# remotecontrol.net
KiCad netlist of a schematic drawn in EAGLE
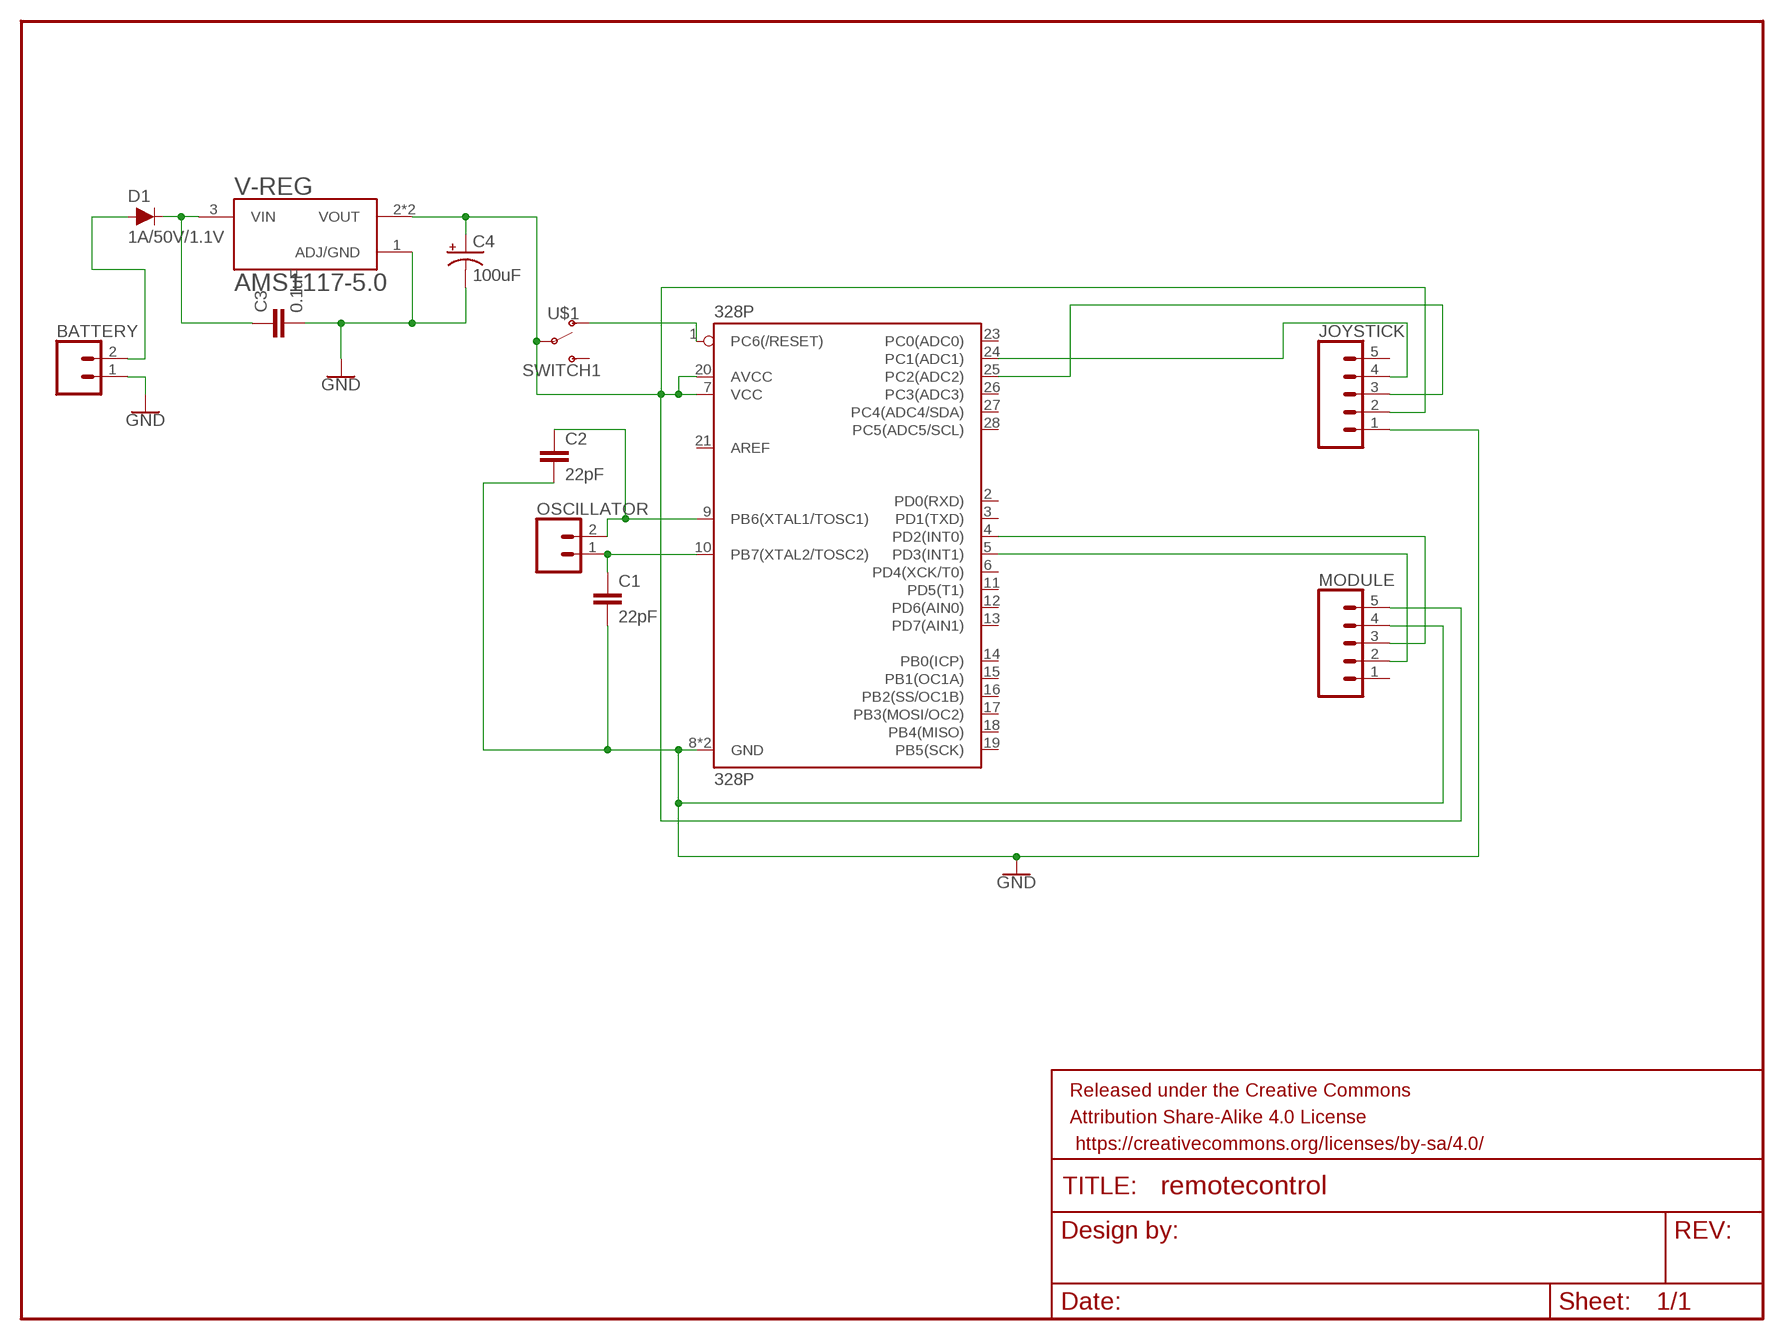
[diagram p0: schematic, sheet 1]

(export (version "E")
  (design (tool "Eeschema 10.0.6"))
  (components
    (comp (ref "328P")
      (value "328P")
      (footprint "eagle-import:DIP28")
      (libsource (lib "eagle-import") (part "ATMEGA328P_PDIP"))
    )
    (comp (ref "BATTERY")
      (value "CONN_02")
      (footprint "eagle-import:1X02")
      (libsource (lib "eagle-import") (part "CONN_02"))
    )
    (comp (ref "C1")
      (value "22pF")
      (footprint "eagle-import:0603")
      (libsource (lib "eagle-import") (part "22PF-0603-50V-5%"))
    )
    (comp (ref "C2")
      (value "22pF")
      (footprint "eagle-import:0603")
      (libsource (lib "eagle-import") (part "22PF-0603-50V-5%"))
    )
    (comp (ref "C3")
      (value "0.1uF")
      (footprint "eagle-import:0603")
      (libsource (lib "eagle-import") (part "0.1UF-0603-25V-(+80/-20%)"))
    )
    (comp (ref "C4")
      (value "100uF")
      (footprint "eagle-import:NIC_10X10.5_CAP")
      (libsource (lib "eagle-import") (part "100UF-POLAR-10X10.5-63V-20%"))
    )
    (comp (ref "D1")
      (value "1A/50V/1.1V")
      (footprint "eagle-import:DIODE-1N4001")
      (libsource (lib "eagle-import") (part "DIODE-PTH"))
    )
    (comp (ref "FRAME1")
      (value "FRAME-LETTER")
      (footprint "eagle-import:CREATIVE_COMMONS")
      (libsource (lib "eagle-import") (part "FRAME-LETTER"))
    )
    (comp (ref "JOYSTICK")
      (value "CONN_05")
      (footprint "eagle-import:1X05")
      (libsource (lib "eagle-import") (part "CONN_05"))
    )
    (comp (ref "MODULE")
      (value "CONN_05")
      (footprint "eagle-import:1X05")
      (libsource (lib "eagle-import") (part "CONN_05"))
    )
    (comp (ref "OSCILLATOR")
      (value "CONN_02")
      (footprint "eagle-import:1X02")
      (libsource (lib "eagle-import") (part "CONN_02"))
    )
    (comp (ref "U$1")
      (value "SWITCH1")
      (footprint "eagle-import:SWITCH1")
      (libsource (lib "eagle-import") (part "SWITCH1"))
    )
    (comp (ref "V-REG")
      (value "AMS1117-5.0")
      (footprint "eagle-import:SOT229P700X180-4N")
      (fields (field (name "MF") "Advanced Monolithic Systems"))
      (libsource (lib "eagle-import") (part "AMS1117-5.0"))
    )
  )
  (nets
    (net (code "1") (name "GND") (class "Default")
      (node (ref "328P") (pin "22") (pinfunction "GND_22") (pintype "bidirectional"))
      (node (ref "328P") (pin "8") (pinfunction "GND_8") (pintype "bidirectional"))
      (node (ref "BATTERY") (pin "1") (pinfunction "1_1") (pintype "passive"))
      (node (ref "C1") (pin "2") (pinfunction "2_2") (pintype "passive"))
      (node (ref "C2") (pin "2") (pinfunction "2_2") (pintype "passive"))
      (node (ref "C3") (pin "2") (pinfunction "2_2") (pintype "passive"))
      (node (ref "C4") (pin "-") (pinfunction "-_-") (pintype "passive"))
      (node (ref "JOYSTICK") (pin "1") (pinfunction "1_1") (pintype "passive"))
      (node (ref "MODULE") (pin "4") (pinfunction "4_4") (pintype "passive"))
      (node (ref "V-REG") (pin "1") (pinfunction "ADJ/GND_1") (pintype "power_in"))
    )
    (net (code "2") (name "Net-(328P-AVCC)") (class "Default")
      (node (ref "328P") (pin "20") (pinfunction "AVCC_20") (pintype "bidirectional"))
      (node (ref "328P") (pin "7") (pinfunction "VCC_7") (pintype "bidirectional"))
      (node (ref "C4") (pin "+") (pinfunction "+_+") (pintype "passive"))
      (node (ref "JOYSTICK") (pin "2") (pinfunction "2_2") (pintype "passive"))
      (node (ref "MODULE") (pin "5") (pinfunction "5_5") (pintype "passive"))
      (node (ref "U$1") (pin "P$2") (pinfunction "P_P$2") (pintype "passive"))
      (node (ref "V-REG") (pin "2") (pinfunction "VOUT_2") (pintype "output"))
      (node (ref "V-REG") (pin "4") (pinfunction "VOUT_4") (pintype "output"))
    )
    (net (code "3") (name "Net-(328P-PB6(XTAL1{slash}TOSC1))") (class "Default")
      (node (ref "328P") (pin "9") (pinfunction "PB6(XTAL1/TOSC1)_9") (pintype "bidirectional"))
      (node (ref "C2") (pin "1") (pinfunction "1_1") (pintype "passive"))
      (node (ref "OSCILLATOR") (pin "2") (pinfunction "2_2") (pintype "passive"))
    )
    (net (code "4") (name "Net-(328P-PB7(XTAL2{slash}TOSC2))") (class "Default")
      (node (ref "328P") (pin "10") (pinfunction "PB7(XTAL2/TOSC2)_10") (pintype "bidirectional"))
      (node (ref "C1") (pin "1") (pinfunction "1_1") (pintype "passive"))
      (node (ref "OSCILLATOR") (pin "1") (pinfunction "1_1") (pintype "passive"))
    )
    (net (code "5") (name "Net-(328P-PC1(ADC1))") (class "Default")
      (node (ref "328P") (pin "24") (pinfunction "PC1(ADC1)_24") (pintype "bidirectional"))
      (node (ref "JOYSTICK") (pin "4") (pinfunction "4_4") (pintype "passive"))
    )
    (net (code "6") (name "Net-(328P-PC2(ADC2))") (class "Default")
      (node (ref "328P") (pin "25") (pinfunction "PC2(ADC2)_25") (pintype "bidirectional"))
      (node (ref "JOYSTICK") (pin "3") (pinfunction "3_3") (pintype "passive"))
    )
    (net (code "7") (name "Net-(328P-PC6({slash}RESET))") (class "Default")
      (node (ref "328P") (pin "1") (pinfunction "PC6(/RESET)_1") (pintype "bidirectional"))
      (node (ref "U$1") (pin "P$3") (pinfunction "O_P$3") (pintype "passive"))
    )
    (net (code "8") (name "Net-(328P-PD2(INT0))") (class "Default")
      (node (ref "328P") (pin "4") (pinfunction "PD2(INT0)_4") (pintype "bidirectional"))
      (node (ref "MODULE") (pin "3") (pinfunction "3_3") (pintype "passive"))
    )
    (net (code "9") (name "Net-(328P-PD3(INT1))") (class "Default")
      (node (ref "328P") (pin "5") (pinfunction "PD3(INT1)_5") (pintype "bidirectional"))
      (node (ref "MODULE") (pin "2") (pinfunction "2_2") (pintype "passive"))
    )
    (net (code "10") (name "Net-(BATTERY-Pad2)") (class "Default")
      (node (ref "BATTERY") (pin "2") (pinfunction "2_2") (pintype "passive"))
      (node (ref "D1") (pin "A") (pinfunction "A_A") (pintype "passive"))
    )
    (net (code "11") (name "Net-(V-REG-VIN)") (class "Default")
      (node (ref "C3") (pin "1") (pinfunction "1_1") (pintype "passive"))
      (node (ref "D1") (pin "C") (pinfunction "C_C") (pintype "passive"))
      (node (ref "V-REG") (pin "3") (pinfunction "VIN_3") (pintype "input"))
    )
    (net (code "12") (name "unconnected-(328P-AREF-Pad21)") (class "Default")
      (node (ref "328P") (pin "21") (pinfunction "AREF_21") (pintype "bidirectional"))
    )
    (net (code "13") (name "unconnected-(328P-PB0(ICP)-Pad14)") (class "Default")
      (node (ref "328P") (pin "14") (pinfunction "PB0(ICP)_14") (pintype "bidirectional"))
    )
    (net (code "14") (name "unconnected-(328P-PB1(OC1A)-Pad15)") (class "Default")
      (node (ref "328P") (pin "15") (pinfunction "PB1(OC1A)_15") (pintype "bidirectional"))
    )
    (net (code "15") (name "unconnected-(328P-PB2(SS{slash}OC1B)-Pad16)") (class "Default")
      (node (ref "328P") (pin "16") (pinfunction "PB2(SS/OC1B)_16") (pintype "bidirectional"))
    )
    (net (code "16") (name "unconnected-(328P-PB3(MOSI{slash}OC2)-Pad17)") (class "Default")
      (node (ref "328P") (pin "17") (pinfunction "PB3(MOSI/OC2)_17") (pintype "bidirectional"))
    )
    (net (code "17") (name "unconnected-(328P-PB4(MISO)-Pad18)") (class "Default")
      (node (ref "328P") (pin "18") (pinfunction "PB4(MISO)_18") (pintype "bidirectional"))
    )
    (net (code "18") (name "unconnected-(328P-PB5(SCK)-Pad19)") (class "Default")
      (node (ref "328P") (pin "19") (pinfunction "PB5(SCK)_19") (pintype "bidirectional"))
    )
    (net (code "19") (name "unconnected-(328P-PC0(ADC0)-Pad23)") (class "Default")
      (node (ref "328P") (pin "23") (pinfunction "PC0(ADC0)_23") (pintype "bidirectional"))
    )
    (net (code "20") (name "unconnected-(328P-PC3(ADC3)-Pad26)") (class "Default")
      (node (ref "328P") (pin "26") (pinfunction "PC3(ADC3)_26") (pintype "bidirectional"))
    )
    (net (code "21") (name "unconnected-(328P-PC4(ADC4{slash}SDA)-Pad27)") (class "Default")
      (node (ref "328P") (pin "27") (pinfunction "PC4(ADC4/SDA)_27") (pintype "bidirectional"))
    )
    (net (code "22") (name "unconnected-(328P-PC5(ADC5{slash}SCL)-Pad28)") (class "Default")
      (node (ref "328P") (pin "28") (pinfunction "PC5(ADC5/SCL)_28") (pintype "bidirectional"))
    )
    (net (code "23") (name "unconnected-(328P-PD0(RXD)-Pad2)") (class "Default")
      (node (ref "328P") (pin "2") (pinfunction "PD0(RXD)_2") (pintype "bidirectional"))
    )
    (net (code "24") (name "unconnected-(328P-PD1(TXD)-Pad3)") (class "Default")
      (node (ref "328P") (pin "3") (pinfunction "PD1(TXD)_3") (pintype "bidirectional"))
    )
    (net (code "25") (name "unconnected-(328P-PD4(XCK{slash}T0)-Pad6)") (class "Default")
      (node (ref "328P") (pin "6") (pinfunction "PD4(XCK/T0)_6") (pintype "bidirectional"))
    )
    (net (code "26") (name "unconnected-(328P-PD5(T1)-Pad11)") (class "Default")
      (node (ref "328P") (pin "11") (pinfunction "PD5(T1)_11") (pintype "bidirectional"))
    )
    (net (code "27") (name "unconnected-(328P-PD6(AIN0)-Pad12)") (class "Default")
      (node (ref "328P") (pin "12") (pinfunction "PD6(AIN0)_12") (pintype "bidirectional"))
    )
    (net (code "28") (name "unconnected-(328P-PD7(AIN1)-Pad13)") (class "Default")
      (node (ref "328P") (pin "13") (pinfunction "PD7(AIN1)_13") (pintype "bidirectional"))
    )
    (net (code "29") (name "unconnected-(JOYSTICK-Pad5)") (class "Default")
      (node (ref "JOYSTICK") (pin "5") (pinfunction "5_5") (pintype "passive"))
    )
    (net (code "30") (name "unconnected-(MODULE-Pad1)") (class "Default")
      (node (ref "MODULE") (pin "1") (pinfunction "1_1") (pintype "passive"))
    )
    (net (code "31") (name "unconnected-(U$1-S-PadP$1)") (class "Default")
      (node (ref "U$1") (pin "P$1") (pinfunction "S_P$1") (pintype "passive"))
    )
  )
)
